# NeoPixel.net
KiCad netlist of a schematic drawn in Altium Designer
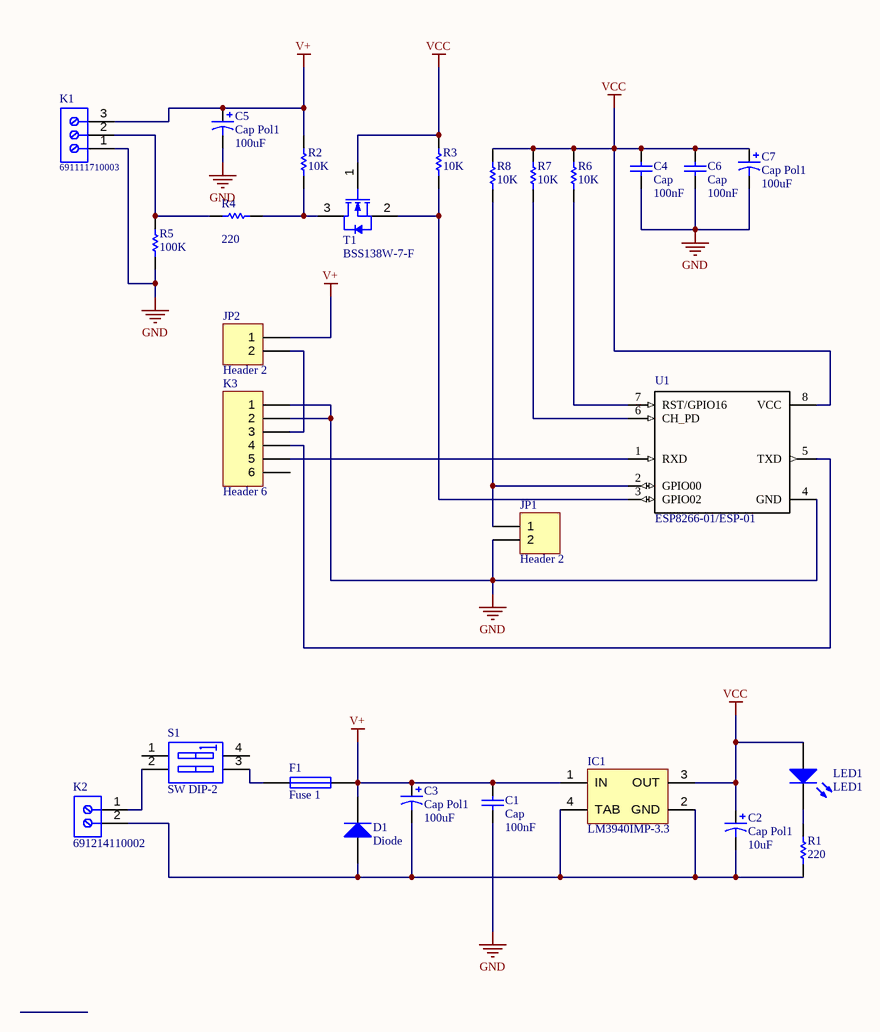
[diagram p0: NeoPixel.SchDoc]

(export (version "E")
  (design (tool "Eeschema 10.0.6"))
  (components
    (comp (ref "C1")
      (value "Cap")
      (footprint "3.2X1.6X1.1")
      (description "Capacitor")
      (fields (field (name "ALTIUM_VALUE") "100nF") (field (name "PUBLISHER") "Altium Limited"))
      (libsource (lib "NeoPixel") (part "Cap"))
    )
    (comp (ref "C2")
      (value "Cap Pol1")
      (footprint "RB7.6-15")
      (description "Polarized Capacitor (Radial)")
      (fields (field (name "ALTIUM_VALUE") "10uF") (field (name "PUBLISHER") "Altium Limited"))
      (libsource (lib "Miscellaneous Devices") (part "Cap Pol1"))
    )
    (comp (ref "C3")
      (value "Cap Pol1")
      (footprint "RB7.6-15")
      (description "Polarized Capacitor (Radial)")
      (fields (field (name "ALTIUM_VALUE") "100uF") (field (name "PUBLISHER") "Altium Limited"))
      (libsource (lib "Miscellaneous Devices") (part "Cap Pol1"))
    )
    (comp (ref "C4")
      (value "Cap")
      (footprint "3.2X1.6X1.1")
      (description "Capacitor")
      (fields (field (name "ALTIUM_VALUE") "100nF") (field (name "PUBLISHER") "Altium Limited"))
      (libsource (lib "NeoPixel") (part "Cap"))
    )
    (comp (ref "C5")
      (value "Cap Pol1")
      (footprint "RB7.6-15")
      (description "Polarized Capacitor (Radial)")
      (fields (field (name "ALTIUM_VALUE") "100uF") (field (name "PUBLISHER") "Altium Limited"))
      (libsource (lib "Miscellaneous Devices") (part "Cap Pol1"))
    )
    (comp (ref "C6")
      (value "Cap")
      (footprint "3.2X1.6X1.1")
      (description "Capacitor")
      (fields (field (name "ALTIUM_VALUE") "100nF") (field (name "PUBLISHER") "Altium Limited"))
      (libsource (lib "NeoPixel") (part "Cap"))
    )
    (comp (ref "C7")
      (value "Cap Pol1")
      (footprint "RB7.6-15")
      (description "Polarized Capacitor (Radial)")
      (fields (field (name "ALTIUM_VALUE") "100uF") (field (name "PUBLISHER") "Altium Limited"))
      (libsource (lib "Miscellaneous Devices") (part "Cap Pol1"))
    )
    (comp (ref "D1")
      (value "Diode")
      (footprint "SMC")
      (description "Default Diode")
      (fields (field (name "PUBLISHER") "Altium Limited"))
      (libsource (lib "Miscellaneous Devices") (part "Diode"))
    )
    (comp (ref "F1")
      (value "Fuse 1")
      (footprint "PIN-W2/E2.8")
      (description "Fuse")
      (fields (field (name "PUBLISHER") "Altium Limited"))
      (libsource (lib "Miscellaneous Devices") (part "Fuse 1"))
    )
    (comp (ref "IC1")
      (value "LM3940IMP-3.3")
      (footprint "DCY0004A_L")
      (description "1A Low Dropout Regulator for 5V to 3.3V Conversion, 4-pin SOT-223")
      (fields (field (name "MANUFACTURER") "Texas Instruments"))
      (libsource (lib "Altium Content Vault") (part "PM-REG-LM2940-TO4"))
    )
    (comp (ref "JP1")
      (value "Header 2")
      (footprint "HDR1X2")
      (description "Header, 2-Pin")
      (fields (field (name "PUBLISHER") "Altium Limited"))
      (libsource (lib "") (part "Header 2_1"))
    )
    (comp (ref "JP2")
      (value "Header 2")
      (footprint "HDR1X2")
      (description "Header, 2-Pin")
      (fields (field (name "PUBLISHER") "Altium Limited"))
      (libsource (lib "Miscellaneous Connectors") (part "Header 2"))
    )
    (comp (ref "K1")
      (value "691111710003")
      (footprint "691111710003")
      (description "Series 111 - 5.00 mm Horizontal Entry Modular with Pressure Clamp WR-TBL, 3 pin")
      (fields (field (name "MANUFACTURER") "Wurth Elektronik") (field (name "PUBLISHER") "WurthElektronik"))
      (libsource (lib "Altium Content Vault") (part "WE-CN-1P-F-TB3"))
    )
    (comp (ref "K2")
      (value "691214110002")
      (footprint "691214110002")
      (description "Serie 2141 - 3.50 mm Horizontal Entry Modular with Rising Cage Clamp WR-TBL, 2 pin")
      (fields (field (name "MANUFACTURER") "Wurth Elektronik") (field (name "PUBLISHER") "WurthElektronik"))
      (libsource (lib "Altium Content Vault") (part "WE-CN-1P-F-TB2"))
    )
    (comp (ref "K3")
      (value "Header 6")
      (footprint "HDR1X6")
      (description "Header, 6-Pin")
      (fields (field (name "PUBLISHER") "Altium Limited"))
      (libsource (lib "Miscellaneous Connectors") (part "Header 6"))
    )
    (comp (ref "LED1")
      (value "LED1")
      (footprint "LED-1")
      (description "Typical RED GaAs LED")
      (fields (field (name "PUBLISHER") "Altium Limited"))
      (libsource (lib "Miscellaneous Devices") (part "LED1"))
    )
    (comp (ref "R1")
      (value "220")
      (footprint "3.2X1.6X1.1")
      (description "Resistor")
      (fields (field (name "Comment") "Res1") (field (name "PUBLISHER") "Altium Limited"))
      (libsource (lib "Miscellaneous Devices") (part "Res1"))
    )
    (comp (ref "R2")
      (value "10K")
      (footprint "3.2X1.6X1.1")
      (description "Resistor")
      (fields (field (name "Comment") "Res1") (field (name "PUBLISHER") "Altium Limited"))
      (libsource (lib "Miscellaneous Devices") (part "Res1"))
    )
    (comp (ref "R3")
      (value "10K")
      (footprint "3.2X1.6X1.1")
      (description "Resistor")
      (fields (field (name "Comment") "Res1") (field (name "PUBLISHER") "Altium Limited"))
      (libsource (lib "Miscellaneous Devices") (part "Res1"))
    )
    (comp (ref "R4")
      (value "220")
      (footprint "3.2X1.6X1.1")
      (description "Resistor")
      (fields (field (name "Comment") "Res1") (field (name "PUBLISHER") "Altium Limited"))
      (libsource (lib "Miscellaneous Devices") (part "Res1"))
    )
    (comp (ref "R5")
      (value "100K")
      (footprint "3.2X1.6X1.1")
      (description "Resistor")
      (fields (field (name "Comment") "Res1") (field (name "PUBLISHER") "Altium Limited"))
      (libsource (lib "Miscellaneous Devices") (part "Res1"))
    )
    (comp (ref "R6")
      (value "10K")
      (footprint "3.2X1.6X1.1")
      (description "Resistor")
      (fields (field (name "Comment") "Res1") (field (name "PUBLISHER") "Altium Limited"))
      (libsource (lib "Miscellaneous Devices") (part "Res1"))
    )
    (comp (ref "R7")
      (value "10K")
      (footprint "3.2X1.6X1.1")
      (description "Resistor")
      (fields (field (name "Comment") "Res1") (field (name "PUBLISHER") "Altium Limited"))
      (libsource (lib "Miscellaneous Devices") (part "Res1"))
    )
    (comp (ref "R8")
      (value "10K")
      (footprint "3.2X1.6X1.1")
      (description "Resistor")
      (fields (field (name "Comment") "Res1") (field (name "PUBLISHER") "Altium Limited"))
      (libsource (lib "Miscellaneous Devices") (part "Res1"))
    )
    (comp (ref "S1")
      (value "SW DIP-2")
      (footprint "DIP-4")
      (description "DIP Switch, 2 Position, SPST")
      (fields (field (name "PUBLISHER") "Altium Limited"))
      (libsource (lib "Miscellaneous Devices") (part "SW DIP-2"))
    )
    (comp (ref "T1")
      (value "BSS138W-7-F")
      (footprint "DIOD-SOT323-3_V")
      (fields (field (name "MANUFACTURER") "DiodesIncorporated"))
      (libsource (lib "Altium Content Vault") (part "NEMOS-GSD-3"))
    )
    (comp (ref "U1")
      (value "ESP8266-01/ESP-01")
      (footprint "*XCVR_ESP8266-01/ESP-01")
      (libsource (lib "ESP8266-01_ESP-01") (part "ESP8266-01/ESP-01"))
    )
  )
  (nets
    (net (code "1") (name "GND") (class "Default")
      (node (ref "C1") (pin "1") (pinfunction "1_1") (pintype "passive"))
      (node (ref "C4") (pin "1") (pinfunction "1_1") (pintype "passive"))
      (node (ref "C5") (pin "2") (pinfunction "2_2") (pintype "passive"))
      (node (ref "C6") (pin "1") (pinfunction "1_1") (pintype "passive"))
      (node (ref "C7") (pin "2") (pinfunction "2_2") (pintype "passive"))
      (node (ref "JP1") (pin "2") (pinfunction "2_2") (pintype "passive"))
      (node (ref "K1") (pin "1") (pinfunction "1_1") (pintype "passive"))
      (node (ref "K3") (pin "1") (pinfunction "1_1") (pintype "passive"))
      (node (ref "K3") (pin "2") (pinfunction "2_2") (pintype "passive"))
      (node (ref "R5") (pin "1") (pinfunction "1_1") (pintype "passive"))
      (node (ref "U1") (pin "4") (pinfunction "GND_4") (pintype "power_in"))
    )
    (net (code "2") (name "Net-(D1-A)") (class "Default")
      (node (ref "C2") (pin "2") (pinfunction "2_2") (pintype "passive"))
      (node (ref "C3") (pin "2") (pinfunction "2_2") (pintype "passive"))
      (node (ref "D1") (pin "1") (pinfunction "A_1") (pintype "passive"))
      (node (ref "IC1") (pin "2") (pinfunction "GND_2") (pintype "power_in"))
      (node (ref "IC1") (pin "4") (pinfunction "TAB_4") (pintype "power_in"))
      (node (ref "K2") (pin "2") (pinfunction "2_2") (pintype "passive"))
      (node (ref "R1") (pin "1") (pinfunction "1_1") (pintype "passive"))
    )
    (net (code "3") (name "Net-(JP2-Pad2)") (class "Default")
      (node (ref "JP2") (pin "2") (pinfunction "2_2") (pintype "passive"))
      (node (ref "K3") (pin "3") (pinfunction "3_3") (pintype "passive"))
    )
    (net (code "4") (name "Net-(K1-Pad2)") (class "Default")
      (node (ref "K1") (pin "2") (pinfunction "2_2") (pintype "passive"))
      (node (ref "R4") (pin "1") (pinfunction "1_1") (pintype "passive"))
      (node (ref "R5") (pin "2") (pinfunction "2_2") (pintype "passive"))
    )
    (net (code "5") (name "Net-(LED1-K)") (class "Default")
      (node (ref "LED1") (pin "2") (pinfunction "K_2") (pintype "passive"))
      (node (ref "R1") (pin "2") (pinfunction "2_2") (pintype "passive"))
    )
    (net (code "6") (name "Net-(S1-A2)") (class "Default")
      (node (ref "K2") (pin "1") (pinfunction "1_1") (pintype "passive"))
      (node (ref "S1") (pin "2") (pinfunction "A2_2") (pintype "passive"))
    )
    (net (code "7") (name "Net-(S1-B2)") (class "Default")
      (node (ref "F1") (pin "1") (pinfunction "1_1") (pintype "passive"))
      (node (ref "S1") (pin "3") (pinfunction "B2_3") (pintype "passive"))
    )
    (net (code "8") (name "Net-(T1-D)") (class "Default")
      (node (ref "R2") (pin "1") (pinfunction "1_1") (pintype "passive"))
      (node (ref "R4") (pin "2") (pinfunction "2_2") (pintype "passive"))
      (node (ref "T1") (pin "3") (pinfunction "D_3") (pintype "passive"))
    )
    (net (code "9") (name "Net-(T1-S)") (class "Default")
      (node (ref "R3") (pin "1") (pinfunction "1_1") (pintype "passive"))
      (node (ref "T1") (pin "2") (pinfunction "S_2") (pintype "passive"))
      (node (ref "U1") (pin "3") (pinfunction "GPIO02_3") (pintype "bidirectional"))
    )
    (net (code "10") (name "Net-(U1-CH_PD)") (class "Default")
      (node (ref "R7") (pin "1") (pinfunction "1_1") (pintype "passive"))
      (node (ref "U1") (pin "6") (pinfunction "CH_PD_6") (pintype "input"))
    )
    (net (code "11") (name "Net-(U1-GPIO00)") (class "Default")
      (node (ref "JP1") (pin "1") (pinfunction "1_1") (pintype "passive"))
      (node (ref "R8") (pin "1") (pinfunction "1_1") (pintype "passive"))
      (node (ref "U1") (pin "2") (pinfunction "GPIO00_2") (pintype "bidirectional"))
    )
    (net (code "12") (name "Net-(U1-RST{slash}GPIO16)") (class "Default")
      (node (ref "R6") (pin "1") (pinfunction "1_1") (pintype "passive"))
      (node (ref "U1") (pin "7") (pinfunction "RST/GPIO16_7") (pintype "input"))
    )
    (net (code "13") (name "Net-(U1-RXD)") (class "Default")
      (node (ref "K3") (pin "5") (pinfunction "5_5") (pintype "passive"))
      (node (ref "U1") (pin "1") (pinfunction "RXD_1") (pintype "input"))
    )
    (net (code "14") (name "Net-(U1-TXD)") (class "Default")
      (node (ref "K3") (pin "4") (pinfunction "4_4") (pintype "passive"))
      (node (ref "U1") (pin "5") (pinfunction "TXD_5") (pintype "output"))
    )
    (net (code "15") (name "V+") (class "Default")
      (node (ref "C1") (pin "2") (pinfunction "2_2") (pintype "passive"))
      (node (ref "C3") (pin "1") (pinfunction "1_1") (pintype "passive"))
      (node (ref "C5") (pin "1") (pinfunction "1_1") (pintype "passive"))
      (node (ref "D1") (pin "2") (pinfunction "K_2") (pintype "passive"))
      (node (ref "F1") (pin "2") (pinfunction "2_2") (pintype "passive"))
      (node (ref "IC1") (pin "1") (pinfunction "IN_1") (pintype "power_in"))
      (node (ref "JP2") (pin "1") (pinfunction "1_1") (pintype "passive"))
      (node (ref "K1") (pin "3") (pinfunction "3_3") (pintype "passive"))
      (node (ref "R2") (pin "2") (pinfunction "2_2") (pintype "passive"))
    )
    (net (code "16") (name "VCC") (class "Default")
      (node (ref "C2") (pin "1") (pinfunction "1_1") (pintype "passive"))
      (node (ref "C4") (pin "2") (pinfunction "2_2") (pintype "passive"))
      (node (ref "C6") (pin "2") (pinfunction "2_2") (pintype "passive"))
      (node (ref "C7") (pin "1") (pinfunction "1_1") (pintype "passive"))
      (node (ref "IC1") (pin "3") (pinfunction "OUT_3") (pintype "power_in"))
      (node (ref "LED1") (pin "1") (pinfunction "A_1") (pintype "passive"))
      (node (ref "R3") (pin "2") (pinfunction "2_2") (pintype "passive"))
      (node (ref "R6") (pin "2") (pinfunction "2_2") (pintype "passive"))
      (node (ref "R7") (pin "2") (pinfunction "2_2") (pintype "passive"))
      (node (ref "R8") (pin "2") (pinfunction "2_2") (pintype "passive"))
      (node (ref "T1") (pin "1") (pinfunction "G_1") (pintype "passive"))
      (node (ref "U1") (pin "8") (pinfunction "VCC_8") (pintype "power_in"))
    )
    (net (code "17") (name "unconnected-(K3-Pad6)") (class "Default")
      (node (ref "K3") (pin "6") (pinfunction "6_6") (pintype "passive"))
    )
    (net (code "18") (name "unconnected-(S1-A1-Pad1)") (class "Default")
      (node (ref "S1") (pin "1") (pinfunction "A1_1") (pintype "passive"))
    )
    (net (code "19") (name "unconnected-(S1-B1-Pad4)") (class "Default")
      (node (ref "S1") (pin "4") (pinfunction "B1_4") (pintype "passive"))
    )
  )
)
